# untitled.net
KiCad netlist of a schematic drawn in EAGLE
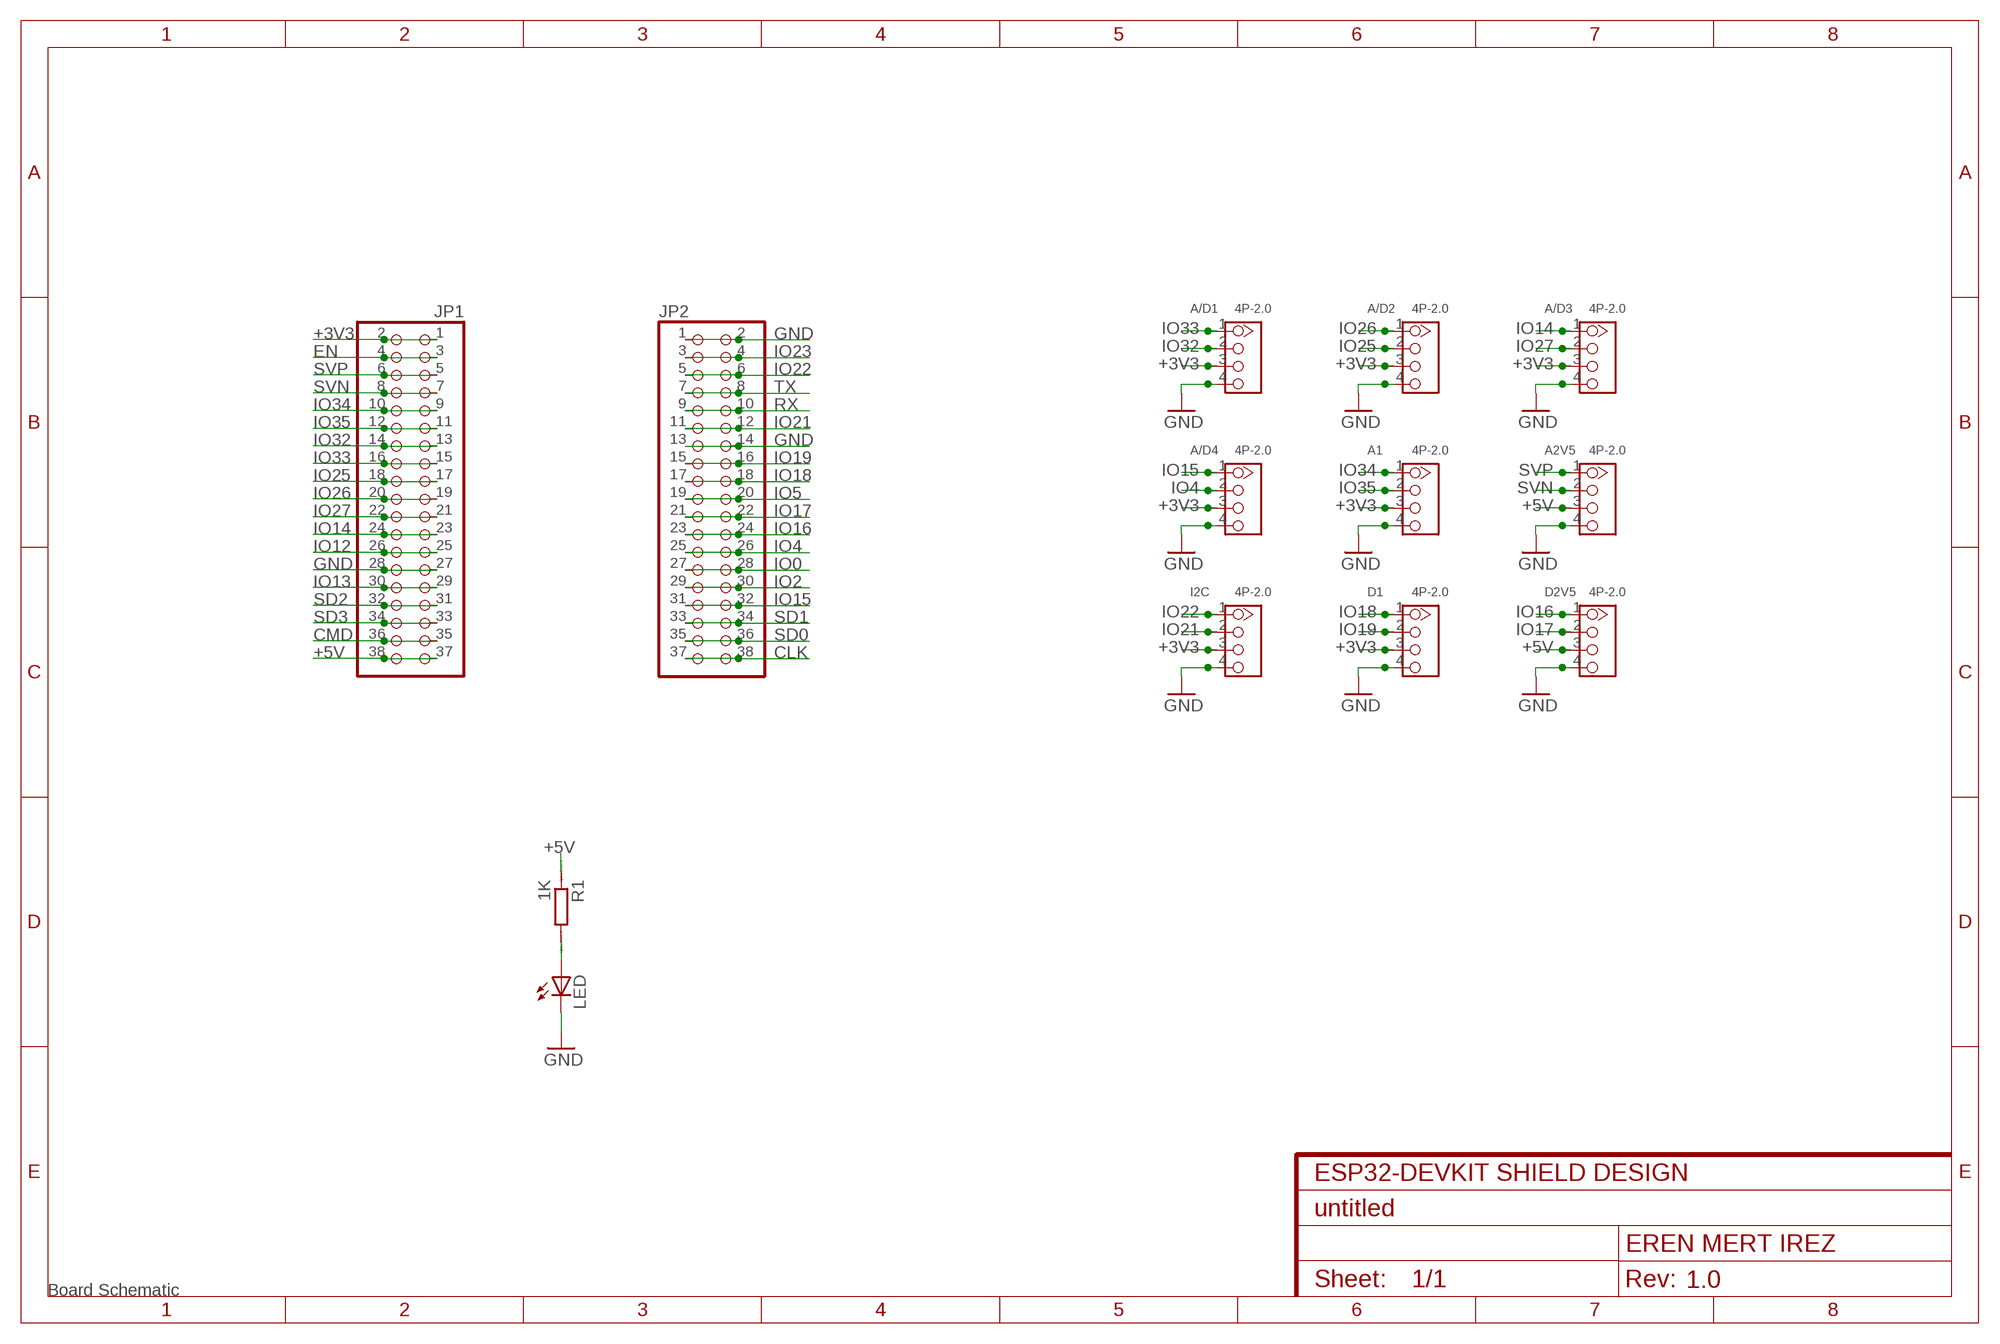
[diagram p0: schematic, sheet 1]

(export (version "E")
  (design (tool "Eeschema 10.0.6"))
  (components
    (comp (ref "A/D1")
      (value "4P-2.0")
      (footprint "eagle-import:HW4-2.0")
      (libsource (lib "eagle-import") (part "GROVE-CONNECTOR-DIP(4P-2.0)"))
    )
    (comp (ref "A/D2")
      (value "4P-2.0")
      (footprint "eagle-import:HW4-2.0")
      (libsource (lib "eagle-import") (part "GROVE-CONNECTOR-DIP(4P-2.0)"))
    )
    (comp (ref "A/D3")
      (value "4P-2.0")
      (footprint "eagle-import:HW4-2.0")
      (libsource (lib "eagle-import") (part "GROVE-CONNECTOR-DIP(4P-2.0)"))
    )
    (comp (ref "A/D4")
      (value "4P-2.0")
      (footprint "eagle-import:HW4-2.0")
      (libsource (lib "eagle-import") (part "GROVE-CONNECTOR-DIP(4P-2.0)"))
    )
    (comp (ref "A1")
      (value "4P-2.0")
      (footprint "eagle-import:HW4-2.0")
      (libsource (lib "eagle-import") (part "GROVE-CONNECTOR-DIP(4P-2.0)"))
    )
    (comp (ref "A2V5")
      (value "4P-2.0")
      (footprint "eagle-import:HW4-2.0")
      (libsource (lib "eagle-import") (part "GROVE-CONNECTOR-DIP(4P-2.0)"))
    )
    (comp (ref "D1")
      (value "4P-2.0")
      (footprint "eagle-import:HW4-2.0")
      (libsource (lib "eagle-import") (part "GROVE-CONNECTOR-DIP(4P-2.0)"))
    )
    (comp (ref "D2V5")
      (value "4P-2.0")
      (footprint "eagle-import:HW4-2.0")
      (libsource (lib "eagle-import") (part "GROVE-CONNECTOR-DIP(4P-2.0)"))
    )
    (comp (ref "I2C")
      (value "4P-2.0")
      (footprint "eagle-import:HW4-2.0")
      (libsource (lib "eagle-import") (part "GROVE-CONNECTOR-DIP(4P-2.0)"))
    )
    (comp (ref "JP1")
      (value "PINHD-2X19")
      (footprint "eagle-import:2X19")
      (libsource (lib "eagle-import") (part "PINHD-2X19"))
    )
    (comp (ref "JP2")
      (value "PINHD-2X19")
      (footprint "eagle-import:2X19")
      (libsource (lib "eagle-import") (part "PINHD-2X19"))
    )
    (comp (ref "LED")
      (value "LED3MM")
      (footprint "eagle-import:LED3MM")
      (libsource (lib "eagle-import") (part "LED3MM"))
    )
    (comp (ref "R1")
      (value "1K")
      (footprint "eagle-import:0207_10")
      (libsource (lib "eagle-import") (part "R0207/10"))
    )
  )
  (nets
    (net (code "1") (name "/+3V3") (class "Default")
      (node (ref "A/D1") (pin "3") (pinfunction "3_3") (pintype "bidirectional"))
      (node (ref "A/D2") (pin "3") (pinfunction "3_3") (pintype "bidirectional"))
      (node (ref "A/D3") (pin "3") (pinfunction "3_3") (pintype "bidirectional"))
      (node (ref "A/D4") (pin "3") (pinfunction "3_3") (pintype "bidirectional"))
      (node (ref "A1") (pin "3") (pinfunction "3_3") (pintype "bidirectional"))
      (node (ref "D1") (pin "3") (pinfunction "3_3") (pintype "bidirectional"))
      (node (ref "I2C") (pin "3") (pinfunction "3_3") (pintype "bidirectional"))
      (node (ref "JP1") (pin "1") (pinfunction "1_1") (pintype "passive"))
      (node (ref "JP1") (pin "2") (pinfunction "2_2") (pintype "passive"))
    )
    (net (code "2") (name "/+5V") (class "Default")
      (node (ref "A2V5") (pin "3") (pinfunction "3_3") (pintype "bidirectional"))
      (node (ref "D2V5") (pin "3") (pinfunction "3_3") (pintype "bidirectional"))
      (node (ref "JP1") (pin "37") (pinfunction "37_37") (pintype "passive"))
      (node (ref "JP1") (pin "38") (pinfunction "38_38") (pintype "passive"))
      (node (ref "R1") (pin "1") (pinfunction "1_1") (pintype "passive"))
    )
    (net (code "3") (name "/CLK") (class "Default")
      (node (ref "JP2") (pin "37") (pinfunction "37_37") (pintype "passive"))
      (node (ref "JP2") (pin "38") (pinfunction "38_38") (pintype "passive"))
    )
    (net (code "4") (name "/CMD") (class "Default")
      (node (ref "JP1") (pin "35") (pinfunction "35_35") (pintype "passive"))
      (node (ref "JP1") (pin "36") (pinfunction "36_36") (pintype "passive"))
    )
    (net (code "5") (name "/EN") (class "Default")
      (node (ref "JP1") (pin "3") (pinfunction "3_3") (pintype "passive"))
      (node (ref "JP1") (pin "4") (pinfunction "4_4") (pintype "passive"))
    )
    (net (code "6") (name "/IO0") (class "Default")
      (node (ref "JP2") (pin "27") (pinfunction "27_27") (pintype "passive"))
      (node (ref "JP2") (pin "28") (pinfunction "28_28") (pintype "passive"))
    )
    (net (code "7") (name "/IO2") (class "Default")
      (node (ref "JP2") (pin "29") (pinfunction "29_29") (pintype "passive"))
      (node (ref "JP2") (pin "30") (pinfunction "30_30") (pintype "passive"))
    )
    (net (code "8") (name "/IO4") (class "Default")
      (node (ref "A/D4") (pin "2") (pinfunction "2_2") (pintype "bidirectional"))
      (node (ref "JP2") (pin "25") (pinfunction "25_25") (pintype "passive"))
      (node (ref "JP2") (pin "26") (pinfunction "26_26") (pintype "passive"))
    )
    (net (code "9") (name "/IO5") (class "Default")
      (node (ref "JP2") (pin "19") (pinfunction "19_19") (pintype "passive"))
      (node (ref "JP2") (pin "20") (pinfunction "20_20") (pintype "passive"))
    )
    (net (code "10") (name "/IO12") (class "Default")
      (node (ref "JP1") (pin "25") (pinfunction "25_25") (pintype "passive"))
      (node (ref "JP1") (pin "26") (pinfunction "26_26") (pintype "passive"))
    )
    (net (code "11") (name "/IO13") (class "Default")
      (node (ref "JP1") (pin "29") (pinfunction "29_29") (pintype "passive"))
      (node (ref "JP1") (pin "30") (pinfunction "30_30") (pintype "passive"))
    )
    (net (code "12") (name "/IO14") (class "Default")
      (node (ref "A/D3") (pin "1") (pinfunction "1_1") (pintype "bidirectional"))
      (node (ref "JP1") (pin "23") (pinfunction "23_23") (pintype "passive"))
      (node (ref "JP1") (pin "24") (pinfunction "24_24") (pintype "passive"))
    )
    (net (code "13") (name "/IO15") (class "Default")
      (node (ref "A/D4") (pin "1") (pinfunction "1_1") (pintype "bidirectional"))
      (node (ref "JP2") (pin "31") (pinfunction "31_31") (pintype "passive"))
      (node (ref "JP2") (pin "32") (pinfunction "32_32") (pintype "passive"))
    )
    (net (code "14") (name "/IO16") (class "Default")
      (node (ref "D2V5") (pin "1") (pinfunction "1_1") (pintype "bidirectional"))
      (node (ref "JP2") (pin "23") (pinfunction "23_23") (pintype "passive"))
      (node (ref "JP2") (pin "24") (pinfunction "24_24") (pintype "passive"))
    )
    (net (code "15") (name "/IO17") (class "Default")
      (node (ref "D2V5") (pin "2") (pinfunction "2_2") (pintype "bidirectional"))
      (node (ref "JP2") (pin "21") (pinfunction "21_21") (pintype "passive"))
      (node (ref "JP2") (pin "22") (pinfunction "22_22") (pintype "passive"))
    )
    (net (code "16") (name "/IO18") (class "Default")
      (node (ref "D1") (pin "1") (pinfunction "1_1") (pintype "bidirectional"))
      (node (ref "JP2") (pin "17") (pinfunction "17_17") (pintype "passive"))
      (node (ref "JP2") (pin "18") (pinfunction "18_18") (pintype "passive"))
    )
    (net (code "17") (name "/IO19") (class "Default")
      (node (ref "D1") (pin "2") (pinfunction "2_2") (pintype "bidirectional"))
      (node (ref "JP2") (pin "15") (pinfunction "15_15") (pintype "passive"))
      (node (ref "JP2") (pin "16") (pinfunction "16_16") (pintype "passive"))
    )
    (net (code "18") (name "/IO21") (class "Default")
      (node (ref "I2C") (pin "2") (pinfunction "2_2") (pintype "bidirectional"))
      (node (ref "JP2") (pin "11") (pinfunction "11_11") (pintype "passive"))
      (node (ref "JP2") (pin "12") (pinfunction "12_12") (pintype "passive"))
    )
    (net (code "19") (name "/IO22") (class "Default")
      (node (ref "I2C") (pin "1") (pinfunction "1_1") (pintype "bidirectional"))
      (node (ref "JP2") (pin "5") (pinfunction "5_5") (pintype "passive"))
      (node (ref "JP2") (pin "6") (pinfunction "6_6") (pintype "passive"))
    )
    (net (code "20") (name "/IO23") (class "Default")
      (node (ref "JP2") (pin "3") (pinfunction "3_3") (pintype "passive"))
      (node (ref "JP2") (pin "4") (pinfunction "4_4") (pintype "passive"))
    )
    (net (code "21") (name "/IO25") (class "Default")
      (node (ref "A/D2") (pin "2") (pinfunction "2_2") (pintype "bidirectional"))
      (node (ref "JP1") (pin "17") (pinfunction "17_17") (pintype "passive"))
      (node (ref "JP1") (pin "18") (pinfunction "18_18") (pintype "passive"))
    )
    (net (code "22") (name "/IO26") (class "Default")
      (node (ref "A/D2") (pin "1") (pinfunction "1_1") (pintype "bidirectional"))
      (node (ref "JP1") (pin "19") (pinfunction "19_19") (pintype "passive"))
      (node (ref "JP1") (pin "20") (pinfunction "20_20") (pintype "passive"))
    )
    (net (code "23") (name "/IO27") (class "Default")
      (node (ref "A/D3") (pin "2") (pinfunction "2_2") (pintype "bidirectional"))
      (node (ref "JP1") (pin "21") (pinfunction "21_21") (pintype "passive"))
      (node (ref "JP1") (pin "22") (pinfunction "22_22") (pintype "passive"))
    )
    (net (code "24") (name "/IO32") (class "Default")
      (node (ref "A/D1") (pin "2") (pinfunction "2_2") (pintype "bidirectional"))
      (node (ref "JP1") (pin "13") (pinfunction "13_13") (pintype "passive"))
      (node (ref "JP1") (pin "14") (pinfunction "14_14") (pintype "passive"))
    )
    (net (code "25") (name "/IO33") (class "Default")
      (node (ref "A/D1") (pin "1") (pinfunction "1_1") (pintype "bidirectional"))
      (node (ref "JP1") (pin "15") (pinfunction "15_15") (pintype "passive"))
      (node (ref "JP1") (pin "16") (pinfunction "16_16") (pintype "passive"))
    )
    (net (code "26") (name "/IO34") (class "Default")
      (node (ref "A1") (pin "1") (pinfunction "1_1") (pintype "bidirectional"))
      (node (ref "JP1") (pin "10") (pinfunction "10_10") (pintype "passive"))
      (node (ref "JP1") (pin "9") (pinfunction "9_9") (pintype "passive"))
    )
    (net (code "27") (name "/IO35") (class "Default")
      (node (ref "A1") (pin "2") (pinfunction "2_2") (pintype "bidirectional"))
      (node (ref "JP1") (pin "11") (pinfunction "11_11") (pintype "passive"))
      (node (ref "JP1") (pin "12") (pinfunction "12_12") (pintype "passive"))
    )
    (net (code "28") (name "/RX") (class "Default")
      (node (ref "JP2") (pin "10") (pinfunction "10_10") (pintype "passive"))
      (node (ref "JP2") (pin "9") (pinfunction "9_9") (pintype "passive"))
    )
    (net (code "29") (name "/SD0") (class "Default")
      (node (ref "JP2") (pin "35") (pinfunction "35_35") (pintype "passive"))
      (node (ref "JP2") (pin "36") (pinfunction "36_36") (pintype "passive"))
    )
    (net (code "30") (name "/SD1") (class "Default")
      (node (ref "JP2") (pin "33") (pinfunction "33_33") (pintype "passive"))
      (node (ref "JP2") (pin "34") (pinfunction "34_34") (pintype "passive"))
    )
    (net (code "31") (name "/SD2") (class "Default")
      (node (ref "JP1") (pin "31") (pinfunction "31_31") (pintype "passive"))
      (node (ref "JP1") (pin "32") (pinfunction "32_32") (pintype "passive"))
    )
    (net (code "32") (name "/SD3") (class "Default")
      (node (ref "JP1") (pin "33") (pinfunction "33_33") (pintype "passive"))
      (node (ref "JP1") (pin "34") (pinfunction "34_34") (pintype "passive"))
    )
    (net (code "33") (name "/SVN") (class "Default")
      (node (ref "A2V5") (pin "2") (pinfunction "2_2") (pintype "bidirectional"))
      (node (ref "JP1") (pin "7") (pinfunction "7_7") (pintype "passive"))
      (node (ref "JP1") (pin "8") (pinfunction "8_8") (pintype "passive"))
    )
    (net (code "34") (name "/SVP") (class "Default")
      (node (ref "A2V5") (pin "1") (pinfunction "1_1") (pintype "bidirectional"))
      (node (ref "JP1") (pin "5") (pinfunction "5_5") (pintype "passive"))
      (node (ref "JP1") (pin "6") (pinfunction "6_6") (pintype "passive"))
    )
    (net (code "35") (name "/TX") (class "Default")
      (node (ref "JP2") (pin "7") (pinfunction "7_7") (pintype "passive"))
      (node (ref "JP2") (pin "8") (pinfunction "8_8") (pintype "passive"))
    )
    (net (code "36") (name "GND") (class "Default")
      (node (ref "A/D1") (pin "4") (pinfunction "4_4") (pintype "bidirectional"))
      (node (ref "A/D2") (pin "4") (pinfunction "4_4") (pintype "bidirectional"))
      (node (ref "A/D3") (pin "4") (pinfunction "4_4") (pintype "bidirectional"))
      (node (ref "A/D4") (pin "4") (pinfunction "4_4") (pintype "bidirectional"))
      (node (ref "A1") (pin "4") (pinfunction "4_4") (pintype "bidirectional"))
      (node (ref "A2V5") (pin "4") (pinfunction "4_4") (pintype "bidirectional"))
      (node (ref "D1") (pin "4") (pinfunction "4_4") (pintype "bidirectional"))
      (node (ref "D2V5") (pin "4") (pinfunction "4_4") (pintype "bidirectional"))
      (node (ref "I2C") (pin "4") (pinfunction "4_4") (pintype "bidirectional"))
      (node (ref "JP1") (pin "27") (pinfunction "27_27") (pintype "passive"))
      (node (ref "JP1") (pin "28") (pinfunction "28_28") (pintype "passive"))
      (node (ref "JP2") (pin "1") (pinfunction "1_1") (pintype "passive"))
      (node (ref "JP2") (pin "13") (pinfunction "13_13") (pintype "passive"))
      (node (ref "JP2") (pin "14") (pinfunction "14_14") (pintype "passive"))
      (node (ref "JP2") (pin "2") (pinfunction "2_2") (pintype "passive"))
      (node (ref "LED") (pin "K") (pinfunction "C_K") (pintype "passive"))
    )
    (net (code "37") (name "Net-(LED-PadA)") (class "Default")
      (node (ref "LED") (pin "A") (pinfunction "A_A") (pintype "passive"))
      (node (ref "R1") (pin "2") (pinfunction "2_2") (pintype "passive"))
    )
  )
)
